# GND_STN.net
KiCad netlist of a schematic drawn in EAGLE
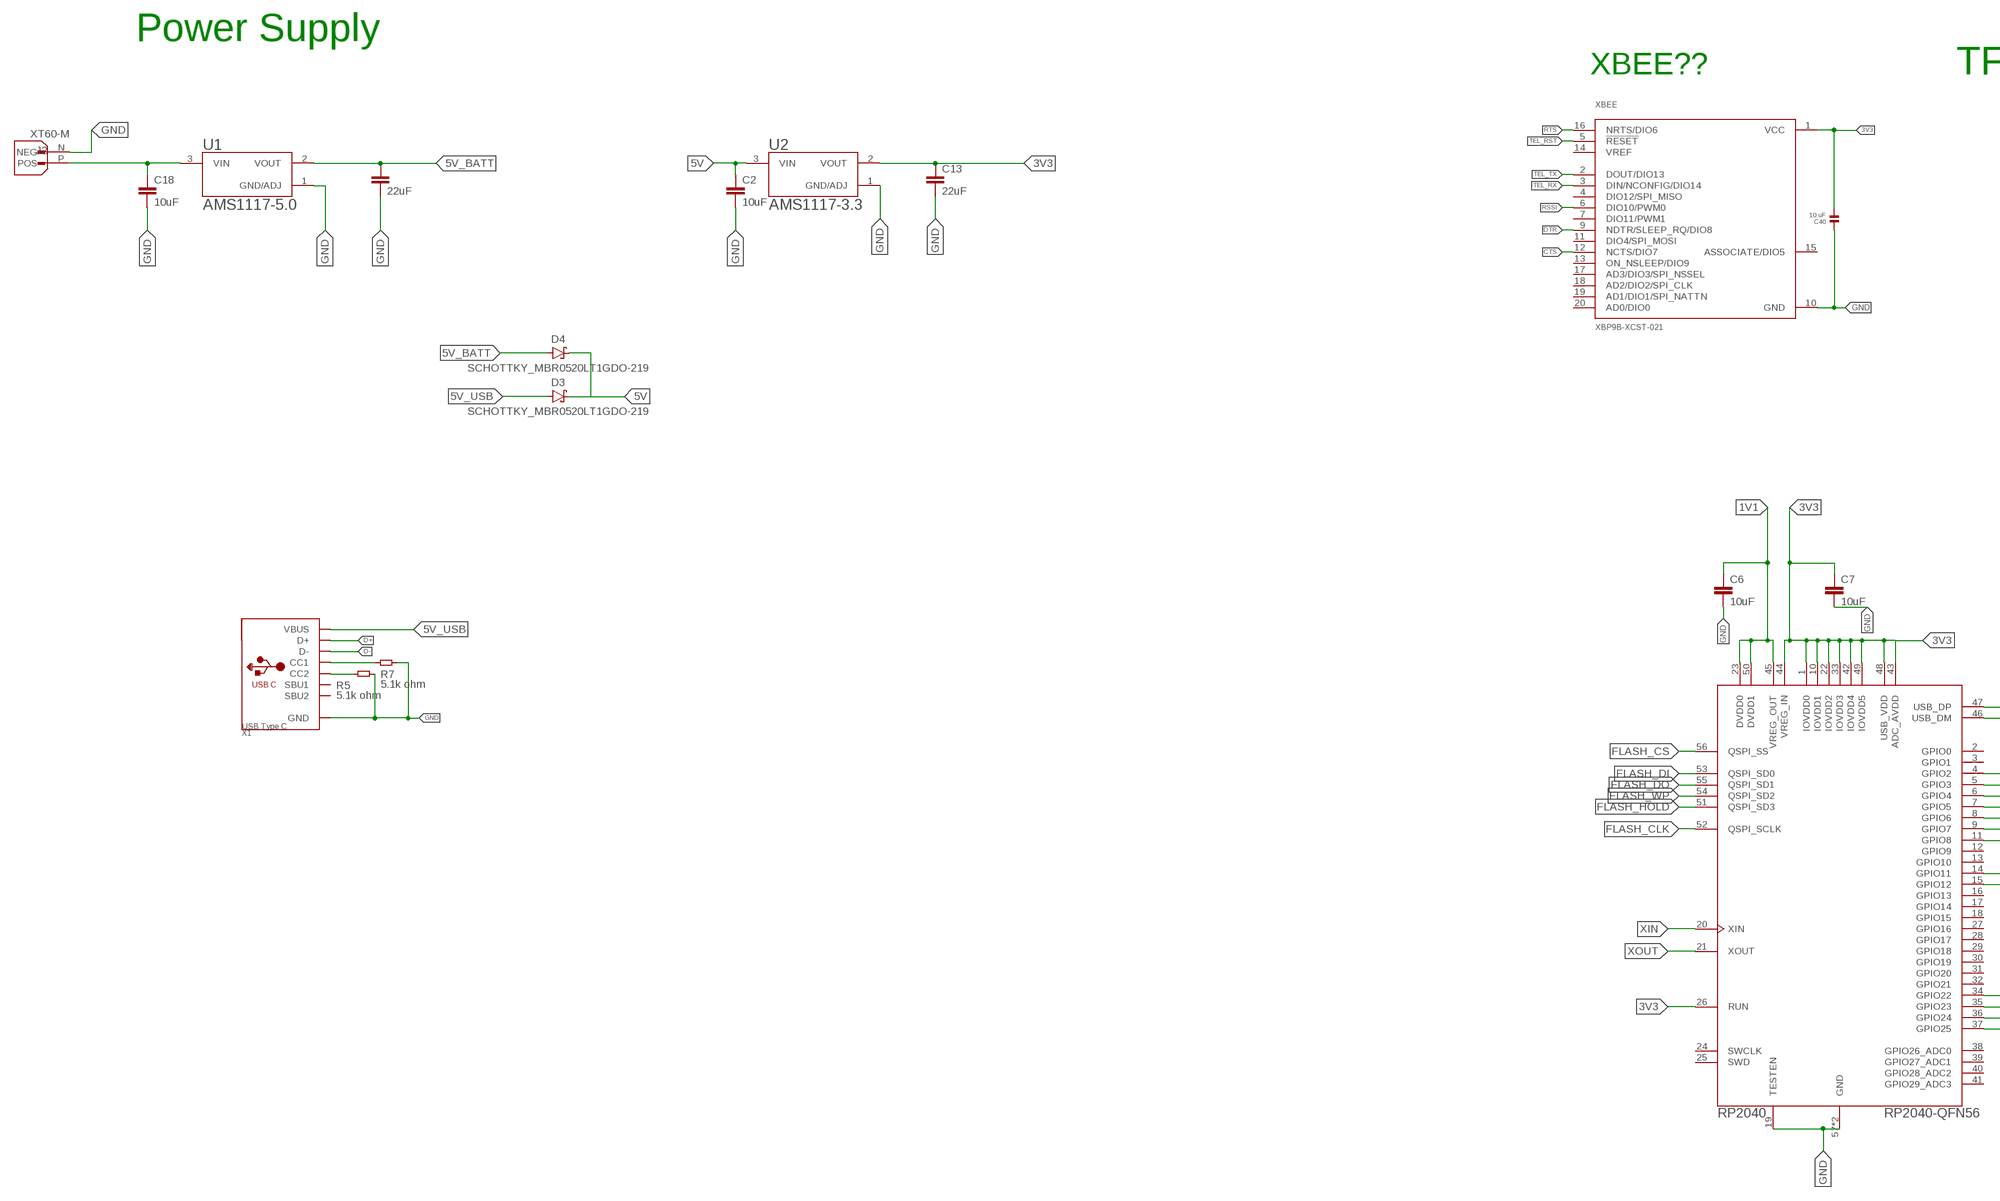
[diagram p0: schematic, sheet 1, part 1 of 2]
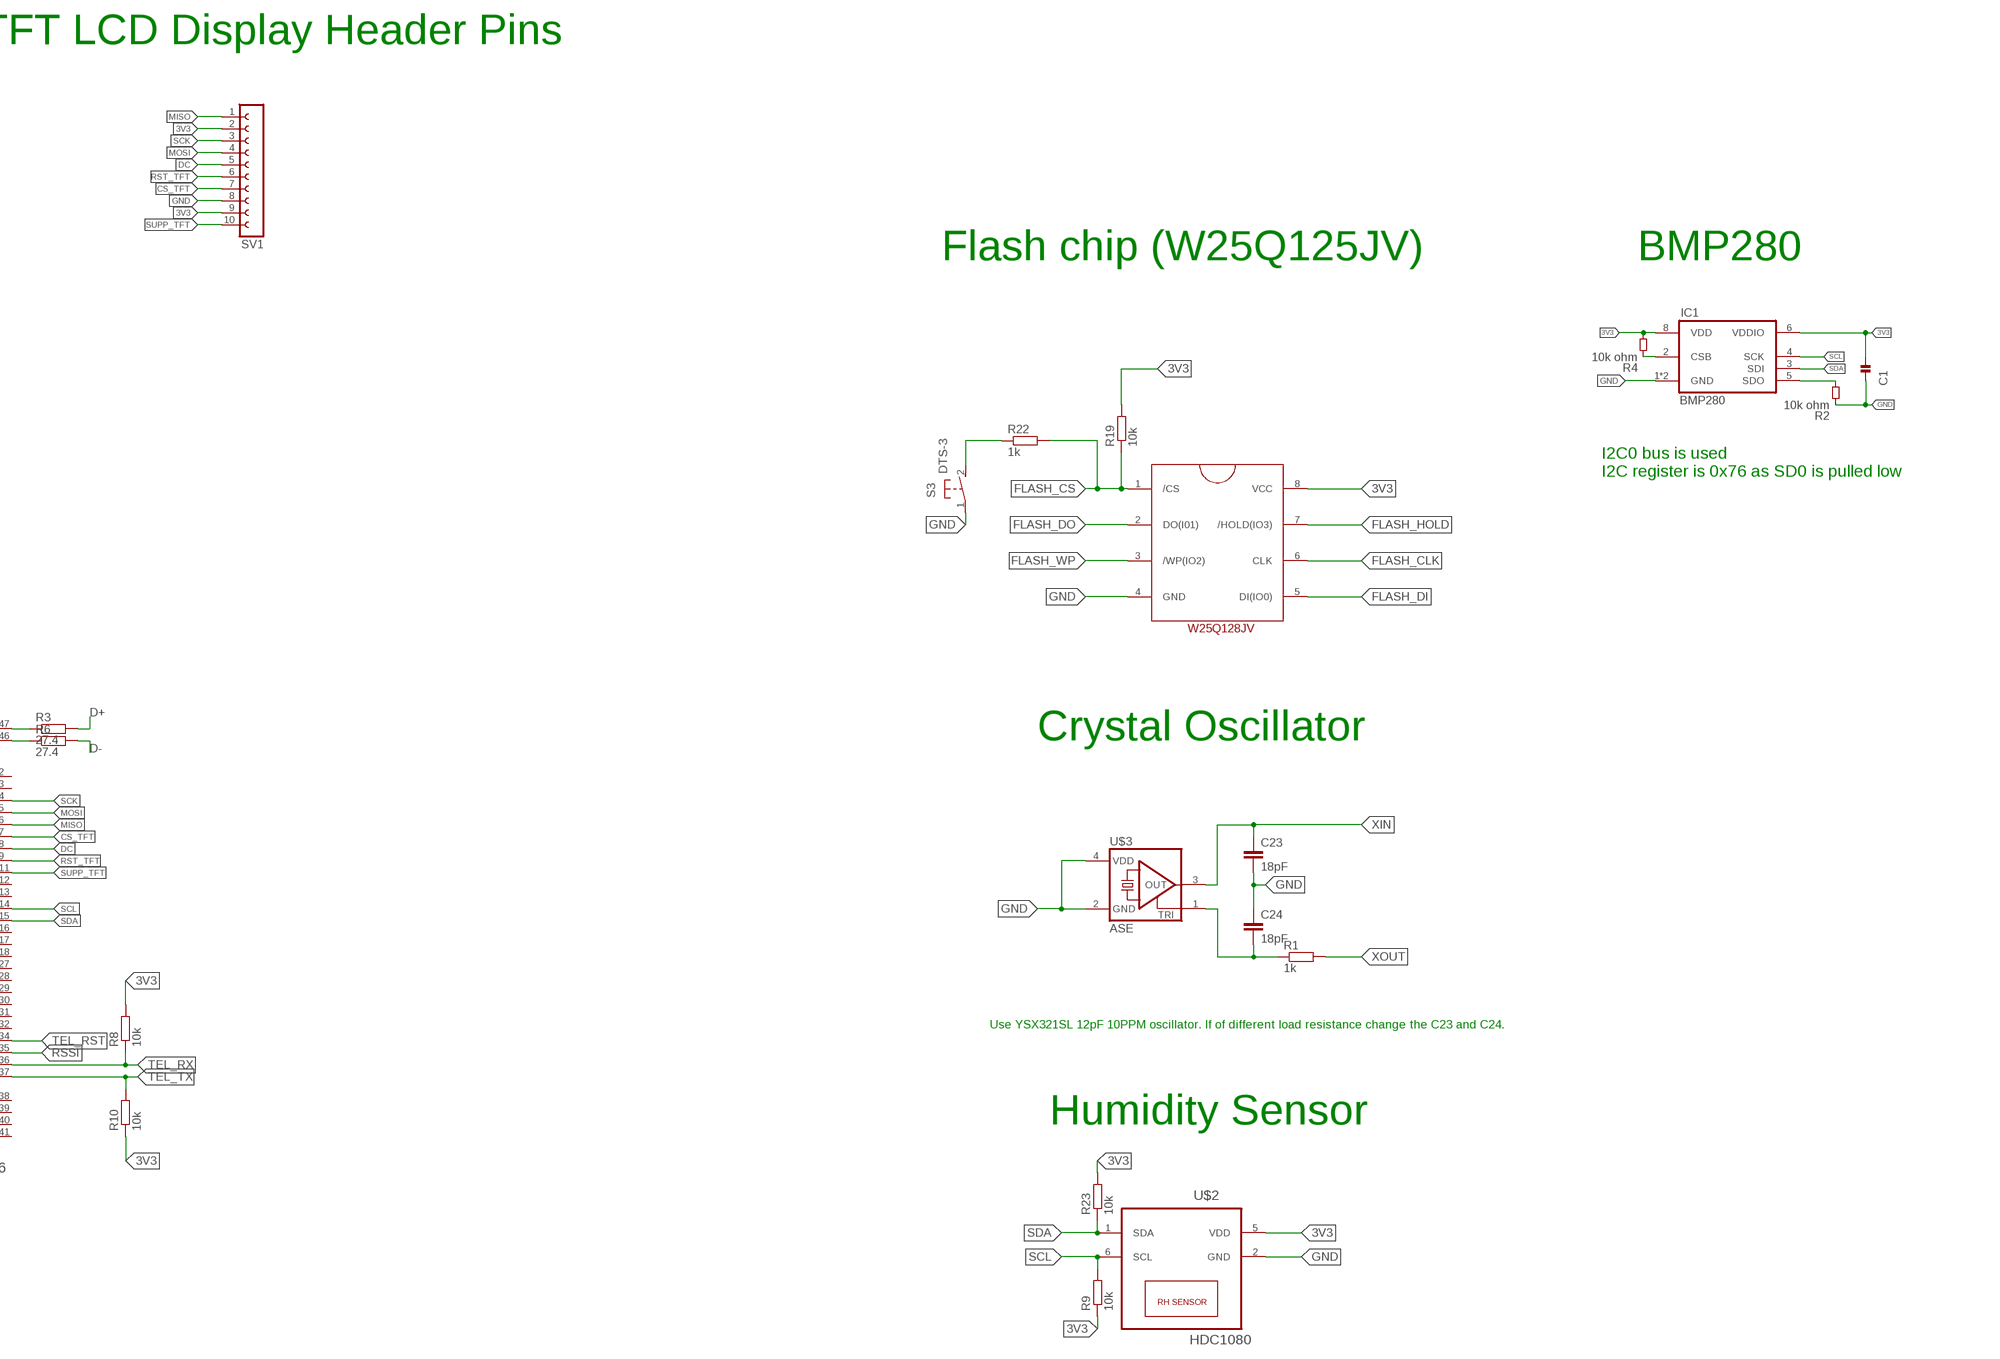
[diagram p1: schematic, sheet 1, part 2 of 2]

(export (version "E")
  (design (tool "Eeschema 10.0.6"))
  (components
    (comp (ref "C1")
      (value "10 uF")
      (footprint "eagle-import:0603")
      (libsource (lib "eagle-import") (part "CAPACITOR.0603"))
    )
    (comp (ref "C2")
      (value "10uF")
      (footprint "eagle-import:C0603")
      (libsource (lib "eagle-import") (part "C-EUC0603"))
    )
    (comp (ref "C3")
      (value "22uF")
      (footprint "eagle-import:C0603")
      (libsource (lib "eagle-import") (part "C-EUC0603"))
    )
    (comp (ref "C6")
      (value "10uF")
      (footprint "eagle-import:C0603")
      (libsource (lib "eagle-import") (part "C-EUC0603"))
    )
    (comp (ref "C7")
      (value "10uF")
      (footprint "eagle-import:C0603")
      (libsource (lib "eagle-import") (part "C-EUC0603"))
    )
    (comp (ref "C13")
      (value "22uF")
      (footprint "eagle-import:C0603")
      (libsource (lib "eagle-import") (part "C-EUC0603"))
    )
    (comp (ref "C18")
      (value "10uF")
      (footprint "eagle-import:C0603")
      (libsource (lib "eagle-import") (part "C-EUC0603"))
    )
    (comp (ref "C23")
      (value "18pF")
      (footprint "eagle-import:C0805")
      (libsource (lib "eagle-import") (part "C-EUC0805"))
    )
    (comp (ref "C24")
      (value "18pF")
      (footprint "eagle-import:C0805")
      (libsource (lib "eagle-import") (part "C-EUC0805"))
    )
    (comp (ref "C40")
      (value "10 uF")
      (footprint "eagle-import:0603")
      (libsource (lib "eagle-import") (part "CAPACITOR.0603"))
    )
    (comp (ref "D3")
      (value "SCHOTTKY_MBR0520LT1GDO-219")
      (footprint "eagle-import:SODFL3718X115")
      (fields (field (name "MANUFACTURER") "onsemi") (field (name "MPN") "MBR0520LT1G"))
      (libsource (lib "eagle-import") (part "SCHOTTKY_DO-219MBR0520LT1G"))
    )
    (comp (ref "D4")
      (value "SCHOTTKY_MBR0520LT1GDO-219")
      (footprint "eagle-import:SODFL3718X115")
      (fields (field (name "MANUFACTURER") "onsemi") (field (name "MPN") "MBR0520LT1G"))
      (libsource (lib "eagle-import") (part "SCHOTTKY_DO-219MBR0520LT1G"))
    )
    (comp (ref "IC1")
      (value "BMP280")
      (footprint "eagle-import:BMP280")
      (libsource (lib "eagle-import") (part "BMP280"))
    )
    (comp (ref "J2")
      (value "XT60-M")
      (footprint "eagle-import:AMASS_XT60-M")
      (fields (field (name "MF") "AMASS"))
      (libsource (lib "eagle-import") (part "XT60-M"))
    )
    (comp (ref "R1")
      (value "1k")
      (footprint "eagle-import:R0805")
      (libsource (lib "eagle-import") (part "R-EU_R0805"))
    )
    (comp (ref "R2")
      (value "10k ohm")
      (footprint "eagle-import:0603")
      (libsource (lib "eagle-import") (part "RESISTOR.0603"))
    )
    (comp (ref "R3")
      (value "27.4")
      (footprint "eagle-import:R0603")
      (libsource (lib "eagle-import") (part "R-EU_R0603"))
    )
    (comp (ref "R4")
      (value "10k ohm")
      (footprint "eagle-import:0603")
      (libsource (lib "eagle-import") (part "RESISTOR.0603"))
    )
    (comp (ref "R5")
      (value "5.1k ohm")
      (footprint "eagle-import:0603")
      (libsource (lib "eagle-import") (part "RESISTOR.0603"))
    )
    (comp (ref "R6")
      (value "27.4")
      (footprint "eagle-import:R0603")
      (libsource (lib "eagle-import") (part "R-EU_R0603"))
    )
    (comp (ref "R7")
      (value "5.1k ohm")
      (footprint "eagle-import:0603")
      (libsource (lib "eagle-import") (part "RESISTOR.0603"))
    )
    (comp (ref "R8")
      (value "10k")
      (footprint "eagle-import:R0603")
      (libsource (lib "eagle-import") (part "R-EU_R0603"))
    )
    (comp (ref "R9")
      (value "10k")
      (footprint "eagle-import:R0603")
      (libsource (lib "eagle-import") (part "R-EU_R0603"))
    )
    (comp (ref "R10")
      (value "10k")
      (footprint "eagle-import:R0603")
      (libsource (lib "eagle-import") (part "R-EU_R0603"))
    )
    (comp (ref "R19")
      (value "10k")
      (footprint "eagle-import:R0603")
      (libsource (lib "eagle-import") (part "R-EU_R0603"))
    )
    (comp (ref "R22")
      (value "1k")
      (footprint "eagle-import:R0603")
      (libsource (lib "eagle-import") (part "R-EU_R0603"))
    )
    (comp (ref "R23")
      (value "10k")
      (footprint "eagle-import:R0603")
      (libsource (lib "eagle-import") (part "R-EU_R0603"))
    )
    (comp (ref "RP2040")
      (value "RP2040-QFN56")
      (footprint "eagle-import:RP2040-QFN-56")
      (libsource (lib "eagle-import") (part "RP2040-QFN56"))
    )
    (comp (ref "S3")
      (value "DTS-3")
      (footprint "eagle-import:DTS-3")
      (fields (field (name "MF") "APEM Inc."))
      (libsource (lib "eagle-import") (part "DTS-3"))
    )
    (comp (ref "SV1")
      (value "FE10-1")
      (footprint "eagle-import:FE10")
      (libsource (lib "eagle-import") (part "FE10-1"))
    )
    (comp (ref "U$2")
      (value "HDC1080")
      (footprint "eagle-import:TI-S-PWSON-N6")
      (libsource (lib "eagle-import") (part "HDC1080"))
    )
    (comp (ref "U$3")
      (value "ASE")
      (footprint "eagle-import:ASE")
      (libsource (lib "eagle-import") (part "ASE"))
    )
    (comp (ref "U1")
      (value "AMS1117-5.0")
      (footprint "eagle-import:SOT229P700X180-4N")
      (fields (field (name "MF") "Advanced Monolithic Systems"))
      (libsource (lib "eagle-import") (part "AMS1117-5.0"))
    )
    (comp (ref "U2")
      (value "AMS1117-3.3")
      (footprint "eagle-import:SOT229P700X180-4N")
      (fields (field (name "MF") "Advanced Monolithic Systems"))
      (libsource (lib "eagle-import") (part "AMS1117-3.3"))
    )
    (comp (ref "U4")
      (value "SOIC127P790X216-8NW25Q128JVJSQ")
      (footprint "eagle-import:SOIC127P790X216-8N")
      (libsource (lib "eagle-import") (part "SOIC127P790X216-8NW25Q128JVJSQ"))
    )
    (comp (ref "X1")
      (value "USB Type C")
      (footprint "eagle-import:USB_C_CUSB31-CFM2AX-01-X")
      (libsource (lib "eagle-import") (part "USB_C"))
    )
    (comp (ref "XBEE")
      (value "XBP9B-XCST-021")
      (footprint "eagle-import:DIP2200W51P200L3294H279Q20P")
      (fields (field (name "MF") "Digi International"))
      (libsource (lib "eagle-import") (part "XBP9B-XCST-021"))
    )
  )
  (nets
    (net (code "1") (name "1V1") (class "Default")
      (node (ref "C6") (pin "1") (pinfunction "1_1") (pintype "passive"))
      (node (ref "RP2040") (pin "23") (pinfunction "DVDD0_23") (pintype "power_in"))
      (node (ref "RP2040") (pin "45") (pinfunction "VREG_OUT_45") (pintype "power_in"))
      (node (ref "RP2040") (pin "50") (pinfunction "DVDD1_50") (pintype "power_in"))
    )
    (net (code "2") (name "3V3") (class "Default")
      (node (ref "C1") (pin "2") (pinfunction "2_2") (pintype "bidirectional"))
      (node (ref "C13") (pin "1") (pinfunction "1_1") (pintype "passive"))
      (node (ref "C40") (pin "2") (pinfunction "2_2") (pintype "bidirectional"))
      (node (ref "C7") (pin "1") (pinfunction "1_1") (pintype "passive"))
      (node (ref "IC1") (pin "6") (pinfunction "VDDIO_6") (pintype "power_in"))
      (node (ref "IC1") (pin "8") (pinfunction "VDD_8") (pintype "power_in"))
      (node (ref "R10") (pin "1") (pinfunction "1_1") (pintype "passive"))
      (node (ref "R19") (pin "2") (pinfunction "2_2") (pintype "passive"))
      (node (ref "R23") (pin "2") (pinfunction "2_2") (pintype "passive"))
      (node (ref "R4") (pin "2") (pinfunction "2_2") (pintype "bidirectional"))
      (node (ref "R8") (pin "2") (pinfunction "2_2") (pintype "passive"))
      (node (ref "R9") (pin "1") (pinfunction "1_1") (pintype "passive"))
      (node (ref "RP2040") (pin "1") (pinfunction "IOVDD0_1") (pintype "power_in"))
      (node (ref "RP2040") (pin "10") (pinfunction "IOVDD1_10") (pintype "power_in"))
      (node (ref "RP2040") (pin "22") (pinfunction "IOVDD2_22") (pintype "power_in"))
      (node (ref "RP2040") (pin "26") (pinfunction "RUN_26") (pintype "input"))
      (node (ref "RP2040") (pin "33") (pinfunction "IOVDD3_33") (pintype "power_in"))
      (node (ref "RP2040") (pin "42") (pinfunction "IOVDD4_42") (pintype "power_in"))
      (node (ref "RP2040") (pin "43") (pinfunction "ADC_AVDD_43") (pintype "power_in"))
      (node (ref "RP2040") (pin "44") (pinfunction "VREG_IN_44") (pintype "power_in"))
      (node (ref "RP2040") (pin "48") (pinfunction "USB_VDD_48") (pintype "power_in"))
      (node (ref "RP2040") (pin "49") (pinfunction "IOVDD5_49") (pintype "power_in"))
      (node (ref "SV1") (pin "2") (pinfunction "2_2") (pintype "passive"))
      (node (ref "SV1") (pin "9") (pinfunction "9_9") (pintype "passive"))
      (node (ref "U$2") (pin "5") (pinfunction "VDD_5") (pintype "output"))
      (node (ref "U2") (pin "2") (pinfunction "VOUT_2") (pintype "output"))
      (node (ref "U4") (pin "8") (pinfunction "VCC_8") (pintype "bidirectional"))
      (node (ref "XBEE") (pin "1") (pinfunction "VCC_1") (pintype "power_in"))
    )
    (net (code "3") (name "5V") (class "Default")
      (node (ref "C2") (pin "1") (pinfunction "1_1") (pintype "passive"))
      (node (ref "D3") (pin "1") (pinfunction "C_1") (pintype "passive"))
      (node (ref "D4") (pin "1") (pinfunction "C_1") (pintype "passive"))
      (node (ref "U2") (pin "3") (pinfunction "VIN_3") (pintype "input"))
    )
    (net (code "4") (name "5V_BATT") (class "Default")
      (node (ref "C3") (pin "1") (pinfunction "1_1") (pintype "passive"))
      (node (ref "D4") (pin "2") (pinfunction "A_2") (pintype "passive"))
      (node (ref "U1") (pin "2") (pinfunction "VOUT_2") (pintype "output"))
    )
    (net (code "5") (name "5V_USB") (class "Default")
      (node (ref "D3") (pin "2") (pinfunction "A_2") (pintype "passive"))
      (node (ref "X1") (pin "A4B9") (pinfunction "VBUS_A4B9") (pintype "power_in"))
      (node (ref "X1") (pin "B4A9") (pinfunction "VBUS_B4A9") (pintype "power_in"))
    )
    (net (code "6") (name "CS_TFT") (class "Default")
      (node (ref "RP2040") (pin "7") (pinfunction "GPIO5_7") (pintype "bidirectional"))
      (node (ref "SV1") (pin "7") (pinfunction "7_7") (pintype "passive"))
    )
    (net (code "7") (name "CTS") (class "Default")
      (node (ref "XBEE") (pin "12") (pinfunction "NCTS/DIO7_12") (pintype "bidirectional"))
    )
    (net (code "8") (name "D+") (class "Default")
      (node (ref "R3") (pin "2") (pinfunction "2_2") (pintype "passive"))
      (node (ref "X1") (pin "A6") (pinfunction "D+_A6") (pintype "bidirectional"))
      (node (ref "X1") (pin "B6") (pinfunction "D+_B6") (pintype "bidirectional"))
    )
    (net (code "9") (name "D-") (class "Default")
      (node (ref "R6") (pin "2") (pinfunction "2_2") (pintype "passive"))
      (node (ref "X1") (pin "A7") (pinfunction "D-_A7") (pintype "bidirectional"))
      (node (ref "X1") (pin "B7") (pinfunction "D-_B7") (pintype "bidirectional"))
    )
    (net (code "10") (name "DC") (class "Default")
      (node (ref "RP2040") (pin "8") (pinfunction "GPIO6_8") (pintype "bidirectional"))
      (node (ref "SV1") (pin "5") (pinfunction "5_5") (pintype "passive"))
    )
    (net (code "11") (name "DTR") (class "Default")
      (node (ref "XBEE") (pin "9") (pinfunction "NDTR/SLEEP_RQ/DIO8_9") (pintype "bidirectional"))
    )
    (net (code "12") (name "FLASH_CLK") (class "Default")
      (node (ref "RP2040") (pin "52") (pinfunction "QSPI_SCLK_52") (pintype "output"))
      (node (ref "U4") (pin "6") (pinfunction "CLK_6") (pintype "bidirectional"))
    )
    (net (code "13") (name "FLASH_CS") (class "Default")
      (node (ref "R19") (pin "1") (pinfunction "1_1") (pintype "passive"))
      (node (ref "R22") (pin "2") (pinfunction "2_2") (pintype "passive"))
      (node (ref "RP2040") (pin "56") (pinfunction "QSPI_SS_56") (pintype "bidirectional"))
      (node (ref "U4") (pin "1") (pinfunction "/CS_1") (pintype "bidirectional"))
    )
    (net (code "14") (name "FLASH_DI") (class "Default")
      (node (ref "RP2040") (pin "53") (pinfunction "QSPI_SD0_53") (pintype "bidirectional"))
      (node (ref "U4") (pin "5") (pinfunction "DI(IO0)_5") (pintype "bidirectional"))
    )
    (net (code "15") (name "FLASH_DO") (class "Default")
      (node (ref "RP2040") (pin "55") (pinfunction "QSPI_SD1_55") (pintype "bidirectional"))
      (node (ref "U4") (pin "2") (pinfunction "DO(I01)_2") (pintype "bidirectional"))
    )
    (net (code "16") (name "FLASH_HOLD") (class "Default")
      (node (ref "RP2040") (pin "51") (pinfunction "QSPI_SD3_51") (pintype "bidirectional"))
      (node (ref "U4") (pin "7") (pinfunction "/HOLD(IO3)_7") (pintype "bidirectional"))
    )
    (net (code "17") (name "FLASH_WP") (class "Default")
      (node (ref "RP2040") (pin "54") (pinfunction "QSPI_SD2_54") (pintype "bidirectional"))
      (node (ref "U4") (pin "3") (pinfunction "/WP(IO2)_3") (pintype "bidirectional"))
    )
    (net (code "18") (name "GND") (class "Default")
      (node (ref "C1") (pin "1") (pinfunction "1_1") (pintype "bidirectional"))
      (node (ref "C13") (pin "2") (pinfunction "2_2") (pintype "passive"))
      (node (ref "C18") (pin "2") (pinfunction "2_2") (pintype "passive"))
      (node (ref "C2") (pin "2") (pinfunction "2_2") (pintype "passive"))
      (node (ref "C23") (pin "2") (pinfunction "2_2") (pintype "passive"))
      (node (ref "C24") (pin "1") (pinfunction "1_1") (pintype "passive"))
      (node (ref "C3") (pin "2") (pinfunction "2_2") (pintype "passive"))
      (node (ref "C40") (pin "1") (pinfunction "1_1") (pintype "bidirectional"))
      (node (ref "C6") (pin "2") (pinfunction "2_2") (pintype "passive"))
      (node (ref "C7") (pin "2") (pinfunction "2_2") (pintype "passive"))
      (node (ref "IC1") (pin "1") (pinfunction "GND_1") (pintype "power_in"))
      (node (ref "IC1") (pin "7") (pinfunction "GND_7") (pintype "power_in"))
      (node (ref "J2") (pin "N") (pinfunction "NEG_N") (pintype "passive"))
      (node (ref "R2") (pin "1") (pinfunction "1_1") (pintype "bidirectional"))
      (node (ref "R5") (pin "2") (pinfunction "2_2") (pintype "bidirectional"))
      (node (ref "R7") (pin "2") (pinfunction "2_2") (pintype "bidirectional"))
      (node (ref "RP2040") (pin "19") (pinfunction "TESTEN_19") (pintype "passive"))
      (node (ref "RP2040") (pin "57") (pinfunction "GND_57") (pintype "power_in"))
      (node (ref "RP2040") (pin "62") (pinfunction "GND_62") (pintype "power_in"))
      (node (ref "S3") (pin "1") (pinfunction "1_1") (pintype "passive"))
      (node (ref "SV1") (pin "8") (pinfunction "8_8") (pintype "passive"))
      (node (ref "U$2") (pin "2") (pinfunction "GND_2") (pintype "passive"))
      (node (ref "U$3") (pin "2") (pinfunction "GND_2") (pintype "power_in"))
      (node (ref "U$3") (pin "4") (pinfunction "VDD_4") (pintype "power_in"))
      (node (ref "U1") (pin "1") (pinfunction "GND/ADJ_1") (pintype "power_in"))
      (node (ref "U2") (pin "1") (pinfunction "GND/ADJ_1") (pintype "power_in"))
      (node (ref "U4") (pin "4") (pinfunction "GND_4") (pintype "bidirectional"))
      (node (ref "X1") (pin "A1B12") (pinfunction "GND_A1B12") (pintype "power_in"))
      (node (ref "X1") (pin "B1A12") (pinfunction "GND_B1A12") (pintype "power_in"))
      (node (ref "XBEE") (pin "10") (pinfunction "GND_10") (pintype "power_in"))
    )
    (net (code "19") (name "MISO") (class "Default")
      (node (ref "RP2040") (pin "6") (pinfunction "GPIO4_6") (pintype "bidirectional"))
      (node (ref "SV1") (pin "1") (pinfunction "1_1") (pintype "passive"))
    )
    (net (code "20") (name "MOSI") (class "Default")
      (node (ref "RP2040") (pin "5") (pinfunction "GPIO3_5") (pintype "bidirectional"))
      (node (ref "SV1") (pin "4") (pinfunction "4_4") (pintype "passive"))
    )
    (net (code "21") (name "Net-(IC1-CSB)") (class "Default")
      (node (ref "IC1") (pin "2") (pinfunction "CSB_2") (pintype "input"))
      (node (ref "R4") (pin "1") (pinfunction "1_1") (pintype "bidirectional"))
    )
    (net (code "22") (name "Net-(IC1-SDO)") (class "Default")
      (node (ref "IC1") (pin "5") (pinfunction "SDO_5") (pintype "input"))
      (node (ref "R2") (pin "2") (pinfunction "2_2") (pintype "bidirectional"))
    )
    (net (code "23") (name "Net-(J2-POS)") (class "Default")
      (node (ref "C18") (pin "1") (pinfunction "1_1") (pintype "passive"))
      (node (ref "J2") (pin "P") (pinfunction "POS_P") (pintype "passive"))
      (node (ref "U1") (pin "3") (pinfunction "VIN_3") (pintype "input"))
    )
    (net (code "24") (name "Net-(R22-Pad1)") (class "Default")
      (node (ref "R22") (pin "1") (pinfunction "1_1") (pintype "passive"))
      (node (ref "S3") (pin "2") (pinfunction "2_2") (pintype "passive"))
    )
    (net (code "25") (name "Net-(RP2040-USB_DM)") (class "Default")
      (node (ref "R6") (pin "1") (pinfunction "1_1") (pintype "passive"))
      (node (ref "RP2040") (pin "46") (pinfunction "USB_DM_46") (pintype "bidirectional"))
    )
    (net (code "26") (name "Net-(RP2040-USB_DP)") (class "Default")
      (node (ref "R3") (pin "1") (pinfunction "1_1") (pintype "passive"))
      (node (ref "RP2040") (pin "47") (pinfunction "USB_DP_47") (pintype "bidirectional"))
    )
    (net (code "27") (name "Net-(U$3-TRI)") (class "Default")
      (node (ref "C24") (pin "2") (pinfunction "2_2") (pintype "passive"))
      (node (ref "R1") (pin "1") (pinfunction "1_1") (pintype "passive"))
      (node (ref "U$3") (pin "1") (pinfunction "TRI_1") (pintype "input"))
    )
    (net (code "28") (name "Net-(X1-CC1)") (class "Default")
      (node (ref "R7") (pin "1") (pinfunction "1_1") (pintype "bidirectional"))
      (node (ref "X1") (pin "A5") (pinfunction "CC1_A5") (pintype "bidirectional"))
    )
    (net (code "29") (name "Net-(X1-CC2)") (class "Default")
      (node (ref "R5") (pin "1") (pinfunction "1_1") (pintype "bidirectional"))
      (node (ref "X1") (pin "B5") (pinfunction "CC2_B5") (pintype "bidirectional"))
    )
    (net (code "30") (name "RSSI") (class "Default")
      (node (ref "RP2040") (pin "35") (pinfunction "GPIO23_35") (pintype "bidirectional"))
      (node (ref "XBEE") (pin "6") (pinfunction "DIO10/PWM0_6") (pintype "bidirectional"))
    )
    (net (code "31") (name "RST_TFT") (class "Default")
      (node (ref "RP2040") (pin "9") (pinfunction "GPIO7_9") (pintype "bidirectional"))
      (node (ref "SV1") (pin "6") (pinfunction "6_6") (pintype "passive"))
    )
    (net (code "32") (name "RTS") (class "Default")
      (node (ref "XBEE") (pin "16") (pinfunction "NRTS/DIO6_16") (pintype "input"))
    )
    (net (code "33") (name "SCK") (class "Default")
      (node (ref "RP2040") (pin "4") (pinfunction "GPIO2_4") (pintype "bidirectional"))
      (node (ref "SV1") (pin "3") (pinfunction "3_3") (pintype "passive"))
    )
    (net (code "34") (name "SCL") (class "Default")
      (node (ref "IC1") (pin "4") (pinfunction "SCK_4") (pintype "bidirectional"))
      (node (ref "R9") (pin "2") (pinfunction "2_2") (pintype "passive"))
      (node (ref "RP2040") (pin "14") (pinfunction "GPIO11_14") (pintype "bidirectional"))
      (node (ref "U$2") (pin "6") (pinfunction "SCL_6") (pintype "passive"))
    )
    (net (code "35") (name "SDA") (class "Default")
      (node (ref "IC1") (pin "3") (pinfunction "SDI_3") (pintype "bidirectional"))
      (node (ref "R23") (pin "1") (pinfunction "1_1") (pintype "passive"))
      (node (ref "RP2040") (pin "15") (pinfunction "GPIO12_15") (pintype "bidirectional"))
      (node (ref "U$2") (pin "1") (pinfunction "SDA_1") (pintype "power_in"))
    )
    (net (code "36") (name "SUPP_TFT") (class "Default")
      (node (ref "RP2040") (pin "11") (pinfunction "GPIO8_11") (pintype "bidirectional"))
      (node (ref "SV1") (pin "10") (pinfunction "10_10") (pintype "passive"))
    )
    (net (code "37") (name "TEL_RST") (class "Default")
      (node (ref "RP2040") (pin "34") (pinfunction "GPIO22_34") (pintype "bidirectional"))
      (node (ref "XBEE") (pin "5") (pinfunction "~{RESET}_5") (pintype "input"))
    )
    (net (code "38") (name "TEL_RX") (class "Default")
      (node (ref "R8") (pin "1") (pinfunction "1_1") (pintype "passive"))
      (node (ref "RP2040") (pin "36") (pinfunction "GPIO24_36") (pintype "bidirectional"))
      (node (ref "XBEE") (pin "3") (pinfunction "DIN/NCONFIG/DIO14_3") (pintype "bidirectional"))
    )
    (net (code "39") (name "TEL_TX") (class "Default")
      (node (ref "R10") (pin "2") (pinfunction "2_2") (pintype "passive"))
      (node (ref "RP2040") (pin "37") (pinfunction "GPIO25_37") (pintype "bidirectional"))
      (node (ref "XBEE") (pin "2") (pinfunction "DOUT/DIO13_2") (pintype "bidirectional"))
    )
    (net (code "40") (name "XIN") (class "Default")
      (node (ref "C23") (pin "1") (pinfunction "1_1") (pintype "passive"))
      (node (ref "RP2040") (pin "20") (pinfunction "XIN_20") (pintype "input"))
      (node (ref "U$3") (pin "3") (pinfunction "OUT_3") (pintype "output"))
    )
    (net (code "41") (name "XOUT") (class "Default")
      (node (ref "R1") (pin "2") (pinfunction "2_2") (pintype "passive"))
      (node (ref "RP2040") (pin "21") (pinfunction "XOUT_21") (pintype "passive"))
    )
    (net (code "42") (name "unconnected-(RP2040-GPIO0-Pad2)") (class "Default")
      (node (ref "RP2040") (pin "2") (pinfunction "GPIO0_2") (pintype "bidirectional"))
    )
    (net (code "43") (name "unconnected-(RP2040-GPIO1-Pad3)") (class "Default")
      (node (ref "RP2040") (pin "3") (pinfunction "GPIO1_3") (pintype "bidirectional"))
    )
    (net (code "44") (name "unconnected-(RP2040-GPIO9-Pad12)") (class "Default")
      (node (ref "RP2040") (pin "12") (pinfunction "GPIO9_12") (pintype "bidirectional"))
    )
    (net (code "45") (name "unconnected-(RP2040-GPIO10-Pad13)") (class "Default")
      (node (ref "RP2040") (pin "13") (pinfunction "GPIO10_13") (pintype "bidirectional"))
    )
    (net (code "46") (name "unconnected-(RP2040-GPIO13-Pad16)") (class "Default")
      (node (ref "RP2040") (pin "16") (pinfunction "GPIO13_16") (pintype "bidirectional"))
    )
    (net (code "47") (name "unconnected-(RP2040-GPIO14-Pad17)") (class "Default")
      (node (ref "RP2040") (pin "17") (pinfunction "GPIO14_17") (pintype "bidirectional"))
    )
    (net (code "48") (name "unconnected-(RP2040-GPIO15-Pad18)") (class "Default")
      (node (ref "RP2040") (pin "18") (pinfunction "GPIO15_18") (pintype "bidirectional"))
    )
    (net (code "49") (name "unconnected-(RP2040-GPIO16-Pad27)") (class "Default")
      (node (ref "RP2040") (pin "27") (pinfunction "GPIO16_27") (pintype "bidirectional"))
    )
    (net (code "50") (name "unconnected-(RP2040-GPIO17-Pad28)") (class "Default")
      (node (ref "RP2040") (pin "28") (pinfunction "GPIO17_28") (pintype "bidirectional"))
    )
    (net (code "51") (name "unconnected-(RP2040-GPIO18-Pad29)") (class "Default")
      (node (ref "RP2040") (pin "29") (pinfunction "GPIO18_29") (pintype "bidirectional"))
    )
    (net (code "52") (name "unconnected-(RP2040-GPIO19-Pad30)") (class "Default")
      (node (ref "RP2040") (pin "30") (pinfunction "GPIO19_30") (pintype "bidirectional"))
    )
    (net (code "53") (name "unconnected-(RP2040-GPIO20-Pad31)") (class "Default")
      (node (ref "RP2040") (pin "31") (pinfunction "GPIO20_31") (pintype "bidirectional"))
    )
    (net (code "54") (name "unconnected-(RP2040-GPIO21-Pad32)") (class "Default")
      (node (ref "RP2040") (pin "32") (pinfunction "GPIO21_32") (pintype "bidirectional"))
    )
    (net (code "55") (name "unconnected-(RP2040-GPIO26_ADC0-Pad38)") (class "Default")
      (node (ref "RP2040") (pin "38") (pinfunction "GPIO26_ADC0_38") (pintype "bidirectional"))
    )
    (net (code "56") (name "unconnected-(RP2040-GPIO27_ADC1-Pad39)") (class "Default")
      (node (ref "RP2040") (pin "39") (pinfunction "GPIO27_ADC1_39") (pintype "bidirectional"))
    )
    (net (code "57") (name "unconnected-(RP2040-GPIO28_ADC2-Pad40)") (class "Default")
      (node (ref "RP2040") (pin "40") (pinfunction "GPIO28_ADC2_40") (pintype "bidirectional"))
    )
    (net (code "58") (name "unconnected-(RP2040-GPIO29_ADC3-Pad41)") (class "Default")
      (node (ref "RP2040") (pin "41") (pinfunction "GPIO29_ADC3_41") (pintype "bidirectional"))
    )
    (net (code "59") (name "unconnected-(RP2040-SWCLK-Pad24)") (class "Default")
      (node (ref "RP2040") (pin "24") (pinfunction "SWCLK_24") (pintype "output"))
    )
    (net (code "60") (name "unconnected-(RP2040-SWD-Pad25)") (class "Default")
      (node (ref "RP2040") (pin "25") (pinfunction "SWD_25") (pintype "bidirectional"))
    )
    (net (code "61") (name "unconnected-(X1-SBU1-PadA8)") (class "Default")
      (node (ref "X1") (pin "A8") (pinfunction "SBU1_A8") (pintype "bidirectional"))
    )
    (net (code "62") (name "unconnected-(X1-SBU2-PadB8)") (class "Default")
      (node (ref "X1") (pin "B8") (pinfunction "SBU2_B8") (pintype "bidirectional"))
    )
    (net (code "63") (name "unconnected-(XBEE-AD0{slash}DIO0-Pad20)") (class "Default")
      (node (ref "XBEE") (pin "20") (pinfunction "AD0/DIO0_20") (pintype "bidirectional"))
    )
    (net (code "64") (name "unconnected-(XBEE-AD1{slash}DIO1{slash}SPI_NATTN-Pad19)") (class "Default")
      (node (ref "XBEE") (pin "19") (pinfunction "AD1/DIO1/SPI_NATTN_19") (pintype "bidirectional"))
    )
    (net (code "65") (name "unconnected-(XBEE-AD2{slash}DIO2{slash}SPI_CLK-Pad18)") (class "Default")
      (node (ref "XBEE") (pin "18") (pinfunction "AD2/DIO2/SPI_CLK_18") (pintype "bidirectional"))
    )
    (net (code "66") (name "unconnected-(XBEE-AD3{slash}DIO3{slash}SPI_NSSEL-Pad17)") (class "Default")
      (node (ref "XBEE") (pin "17") (pinfunction "AD3/DIO3/SPI_NSSEL_17") (pintype "bidirectional"))
    )
    (net (code "67") (name "unconnected-(XBEE-ASSOCIATE{slash}DIO5-Pad15)") (class "Default")
      (node (ref "XBEE") (pin "15") (pinfunction "ASSOCIATE/DIO5_15") (pintype "output"))
    )
    (net (code "68") (name "unconnected-(XBEE-DIO4{slash}SPI_MOSI-Pad11)") (class "Default")
      (node (ref "XBEE") (pin "11") (pinfunction "DIO4/SPI_MOSI_11") (pintype "bidirectional"))
    )
    (net (code "69") (name "unconnected-(XBEE-DIO11{slash}PWM1-Pad7)") (class "Default")
      (node (ref "XBEE") (pin "7") (pinfunction "DIO11/PWM1_7") (pintype "bidirectional"))
    )
    (net (code "70") (name "unconnected-(XBEE-DIO12{slash}SPI_MISO-Pad4)") (class "Default")
      (node (ref "XBEE") (pin "4") (pinfunction "DIO12/SPI_MISO_4") (pintype "bidirectional"))
    )
    (net (code "71") (name "unconnected-(XBEE-ON_NSLEEP{slash}DIO9-Pad13)") (class "Default")
      (node (ref "XBEE") (pin "13") (pinfunction "ON_NSLEEP/DIO9_13") (pintype "bidirectional"))
    )
    (net (code "72") (name "unconnected-(XBEE-VREF-Pad14)") (class "Default")
      (node (ref "XBEE") (pin "14") (pinfunction "VREF_14") (pintype "input"))
    )
  )
)
